# L80_Breakout.net
KiCad netlist of a schematic drawn in EAGLE
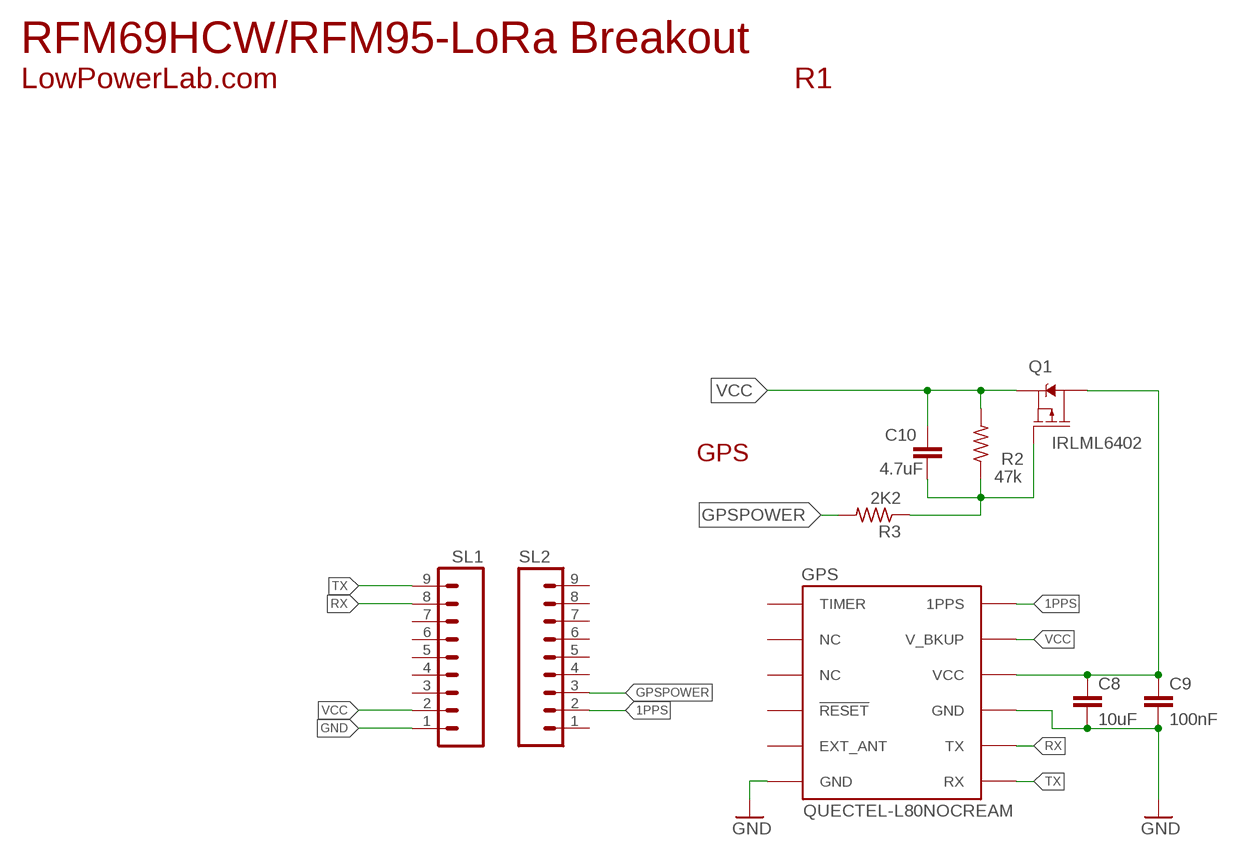
[diagram p0: schematic, sheet 1]

(export (version "E")
  (design (tool "Eeschema 10.0.6"))
  (components
    (comp (ref "C8")
      (value "10uF")
      (footprint "eagle-import:C0603-THINCREAM")
      (libsource (lib "eagle-import") (part "CAPC0603-THINCREAM"))
    )
    (comp (ref "C9")
      (value "100nF")
      (footprint "eagle-import:C0603-THINCREAM")
      (fields (field (name "MF") "AVX") (field (name "MPN") "02016D104KAT2A"))
      (libsource (lib "eagle-import") (part "CAPC0603-THINCREAM"))
    )
    (comp (ref "C10")
      (value "4.7uF")
      (footprint "eagle-import:C0603-THINCREAM")
      (libsource (lib "eagle-import") (part "CAPC0603-THINCREAM"))
    )
    (comp (ref "GPS")
      (value "QUECTEL-L80NOCREAM")
      (footprint "eagle-import:QUECTEL-L80-NOCREAM")
      (libsource (lib "eagle-import") (part "QUECTEL-L80NOCREAM"))
    )
    (comp (ref "Q1")
      (value "IRLML6402")
      (footprint "eagle-import:SOT23-3")
      (libsource (lib "eagle-import") (part "MOSFET_PCH-IRLML6402"))
    )
    (comp (ref "R2")
      (value "47k")
      (footprint "eagle-import:R0603-THINCREAM")
      (libsource (lib "eagle-import") (part "R-USR0603-THINCREAM"))
    )
    (comp (ref "R3")
      (value "2K2")
      (footprint "eagle-import:R0603-THINCREAM")
      (libsource (lib "eagle-import") (part "R-USR0603-THINCREAM"))
    )
    (comp (ref "SL1")
      (value "M09")
      (footprint "eagle-import:09P")
      (libsource (lib "eagle-import") (part "M09"))
    )
    (comp (ref "SL2")
      (value "M09")
      (footprint "eagle-import:09P")
      (libsource (lib "eagle-import") (part "M09"))
    )
  )
  (nets
    (net (code "1") (name "1PPS") (class "Default")
      (node (ref "GPS") (pin "6") (pinfunction "1PPS_6") (pintype "bidirectional"))
      (node (ref "SL2") (pin "2") (pinfunction "2_2") (pintype "passive"))
    )
    (net (code "2") (name "GND") (class "Default")
      (node (ref "C8") (pin "2") (pinfunction "2_2") (pintype "passive"))
      (node (ref "C9") (pin "2") (pinfunction "2_2") (pintype "passive"))
      (node (ref "GPS") (pin "12") (pinfunction "GND_12") (pintype "power_in"))
      (node (ref "GPS") (pin "3") (pinfunction "GND_3") (pintype "power_in"))
      (node (ref "SL1") (pin "1") (pinfunction "1_1") (pintype "passive"))
    )
    (net (code "3") (name "GPSPOWER") (class "Default")
      (node (ref "R3") (pin "2") (pinfunction "2_2") (pintype "passive"))
      (node (ref "SL2") (pin "3") (pinfunction "3_3") (pintype "passive"))
    )
    (net (code "4") (name "Net-(GPS-VCC)") (class "Default")
      (node (ref "C8") (pin "1") (pinfunction "1_1") (pintype "passive"))
      (node (ref "C9") (pin "1") (pinfunction "1_1") (pintype "passive"))
      (node (ref "GPS") (pin "4") (pinfunction "VCC_4") (pintype "power_in"))
      (node (ref "Q1") (pin "3") (pinfunction "D_3") (pintype "bidirectional"))
    )
    (net (code "5") (name "Net-(Q1-G)") (class "Default")
      (node (ref "C10") (pin "2") (pinfunction "2_2") (pintype "passive"))
      (node (ref "Q1") (pin "1") (pinfunction "G_1") (pintype "bidirectional"))
      (node (ref "R2") (pin "1") (pinfunction "1_1") (pintype "passive"))
      (node (ref "R3") (pin "1") (pinfunction "1_1") (pintype "passive"))
    )
    (net (code "6") (name "RX") (class "Default")
      (node (ref "GPS") (pin "2") (pinfunction "TX_2") (pintype "output"))
      (node (ref "SL1") (pin "8") (pinfunction "8_8") (pintype "passive"))
    )
    (net (code "7") (name "TX") (class "Default")
      (node (ref "GPS") (pin "1") (pinfunction "RX_1") (pintype "input"))
      (node (ref "SL1") (pin "9") (pinfunction "9_9") (pintype "passive"))
    )
    (net (code "8") (name "VCC") (class "Default")
      (node (ref "C10") (pin "1") (pinfunction "1_1") (pintype "passive"))
      (node (ref "GPS") (pin "5") (pinfunction "V_BKUP_5") (pintype "power_in"))
      (node (ref "Q1") (pin "2") (pinfunction "S_2") (pintype "bidirectional"))
      (node (ref "R2") (pin "2") (pinfunction "2_2") (pintype "passive"))
      (node (ref "SL1") (pin "2") (pinfunction "2_2") (pintype "passive"))
    )
    (net (code "9") (name "unconnected-(GPS-EXT_ANT-Pad11)") (class "Default")
      (node (ref "GPS") (pin "11") (pinfunction "EXT_ANT_11") (pintype "bidirectional"))
    )
    (net (code "10") (name "unconnected-(GPS-NC-Pad8)") (class "Default")
      (node (ref "GPS") (pin "8") (pinfunction "NC_8") (pintype "no_connect"))
    )
    (net (code "11") (name "unconnected-(GPS-NC-Pad9)") (class "Default")
      (node (ref "GPS") (pin "9") (pinfunction "NC_9") (pintype "no_connect"))
    )
    (net (code "12") (name "unconnected-(GPS-TIMER-Pad7)") (class "Default")
      (node (ref "GPS") (pin "7") (pinfunction "TIMER_7") (pintype "bidirectional"))
    )
    (net (code "13") (name "unconnected-(GPS-~{RESET}-Pad10)") (class "Default")
      (node (ref "GPS") (pin "10") (pinfunction "~{RESET}_10") (pintype "input"))
    )
    (net (code "14") (name "unconnected-(SL1-Pad3)") (class "Default")
      (node (ref "SL1") (pin "3") (pinfunction "3_3") (pintype "passive"))
    )
    (net (code "15") (name "unconnected-(SL1-Pad4)") (class "Default")
      (node (ref "SL1") (pin "4") (pinfunction "4_4") (pintype "passive"))
    )
    (net (code "16") (name "unconnected-(SL1-Pad5)") (class "Default")
      (node (ref "SL1") (pin "5") (pinfunction "5_5") (pintype "passive"))
    )
    (net (code "17") (name "unconnected-(SL1-Pad6)") (class "Default")
      (node (ref "SL1") (pin "6") (pinfunction "6_6") (pintype "passive"))
    )
    (net (code "18") (name "unconnected-(SL1-Pad7)") (class "Default")
      (node (ref "SL1") (pin "7") (pinfunction "7_7") (pintype "passive"))
    )
    (net (code "19") (name "unconnected-(SL2-Pad1)") (class "Default")
      (node (ref "SL2") (pin "1") (pinfunction "1_1") (pintype "passive"))
    )
    (net (code "20") (name "unconnected-(SL2-Pad4)") (class "Default")
      (node (ref "SL2") (pin "4") (pinfunction "4_4") (pintype "passive"))
    )
    (net (code "21") (name "unconnected-(SL2-Pad5)") (class "Default")
      (node (ref "SL2") (pin "5") (pinfunction "5_5") (pintype "passive"))
    )
    (net (code "22") (name "unconnected-(SL2-Pad6)") (class "Default")
      (node (ref "SL2") (pin "6") (pinfunction "6_6") (pintype "passive"))
    )
    (net (code "23") (name "unconnected-(SL2-Pad7)") (class "Default")
      (node (ref "SL2") (pin "7") (pinfunction "7_7") (pintype "passive"))
    )
    (net (code "24") (name "unconnected-(SL2-Pad8)") (class "Default")
      (node (ref "SL2") (pin "8") (pinfunction "8_8") (pintype "passive"))
    )
    (net (code "25") (name "unconnected-(SL2-Pad9)") (class "Default")
      (node (ref "SL2") (pin "9") (pinfunction "9_9") (pintype "passive"))
    )
  )
)
